# jumper_bed_M.net
KiCad netlist of a schematic drawn in EAGLE
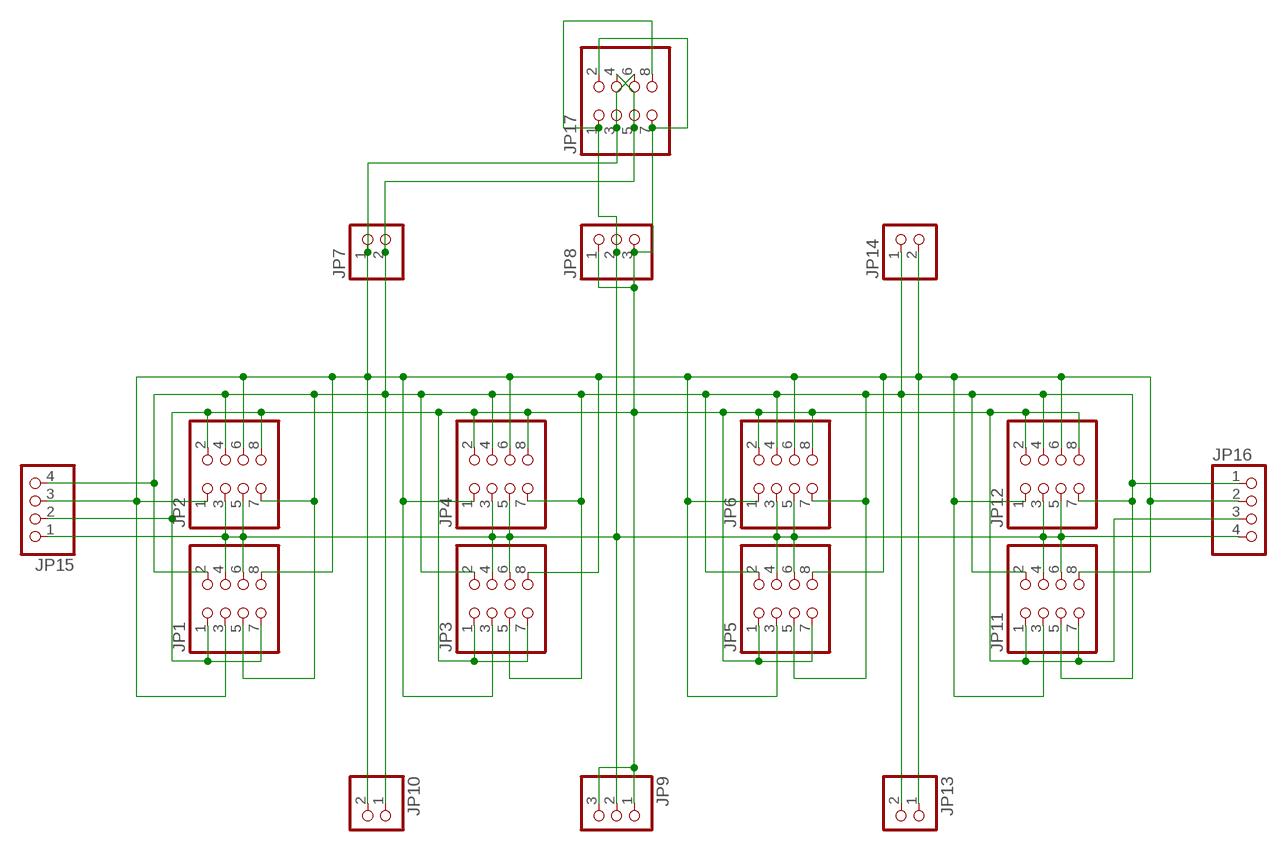
[diagram p0: schematic, sheet 1]

(export (version "E")
  (design (tool "Eeschema 10.0.6"))
  (components
    (comp (ref "JP1")
      (value "PINHD-2X4")
      (footprint "eagle-import:2X04")
      (libsource (lib "eagle-import") (part "PINHD-2X4"))
    )
    (comp (ref "JP2")
      (value "PINHD-2X4")
      (footprint "eagle-import:2X04")
      (libsource (lib "eagle-import") (part "PINHD-2X4"))
    )
    (comp (ref "JP3")
      (value "PINHD-2X4")
      (footprint "eagle-import:2X04")
      (libsource (lib "eagle-import") (part "PINHD-2X4"))
    )
    (comp (ref "JP4")
      (value "PINHD-2X4")
      (footprint "eagle-import:2X04")
      (libsource (lib "eagle-import") (part "PINHD-2X4"))
    )
    (comp (ref "JP5")
      (value "PINHD-2X4")
      (footprint "eagle-import:2X04")
      (libsource (lib "eagle-import") (part "PINHD-2X4"))
    )
    (comp (ref "JP6")
      (value "PINHD-2X4")
      (footprint "eagle-import:2X04")
      (libsource (lib "eagle-import") (part "PINHD-2X4"))
    )
    (comp (ref "JP7")
      (value "PINHD-1X2/90")
      (footprint "eagle-import:1X02_90")
      (libsource (lib "eagle-import") (part "PINHD-1X2/90"))
    )
    (comp (ref "JP8")
      (value "PINHD-1X3/90")
      (footprint "eagle-import:1X03_90")
      (libsource (lib "eagle-import") (part "PINHD-1X3/90"))
    )
    (comp (ref "JP9")
      (value "PINHD-1X31X03/90F")
      (footprint "eagle-import:1X03_90F")
      (libsource (lib "eagle-import") (part "PINHD-1X31X03/90F"))
    )
    (comp (ref "JP10")
      (value "PINHD-1X21X02/90F")
      (footprint "eagle-import:1X02_90F")
      (libsource (lib "eagle-import") (part "PINHD-1X21X02/90F"))
    )
    (comp (ref "JP11")
      (value "PINHD-2X4")
      (footprint "eagle-import:2X04")
      (libsource (lib "eagle-import") (part "PINHD-2X4"))
    )
    (comp (ref "JP12")
      (value "PINHD-2X4")
      (footprint "eagle-import:2X04")
      (libsource (lib "eagle-import") (part "PINHD-2X4"))
    )
    (comp (ref "JP13")
      (value "PINHD-1X21X02/90F")
      (footprint "eagle-import:1X02_90F")
      (libsource (lib "eagle-import") (part "PINHD-1X21X02/90F"))
    )
    (comp (ref "JP14")
      (value "PINHD-1X2/90")
      (footprint "eagle-import:1X02_90")
      (libsource (lib "eagle-import") (part "PINHD-1X2/90"))
    )
    (comp (ref "JP15")
      (value "PINHD-1X4")
      (footprint "eagle-import:1X04")
      (libsource (lib "eagle-import") (part "PINHD-1X4"))
    )
    (comp (ref "JP16")
      (value "PINHD-1X4")
      (footprint "eagle-import:1X04")
      (libsource (lib "eagle-import") (part "PINHD-1X4"))
    )
    (comp (ref "JP17")
      (value "PINHD-2X4/90")
      (footprint "eagle-import:2X04_90")
      (libsource (lib "eagle-import") (part "PINHD-2X4/90"))
    )
  )
  (nets
    (net (code "1") (name "Net-(JP1-Pad1)") (class "Default")
      (node (ref "JP1") (pin "1") (pinfunction "1_1") (pintype "passive"))
      (node (ref "JP1") (pin "7") (pinfunction "7_7") (pintype "passive"))
      (node (ref "JP11") (pin "1") (pinfunction "1_1") (pintype "passive"))
      (node (ref "JP11") (pin "7") (pinfunction "7_7") (pintype "passive"))
      (node (ref "JP12") (pin "2") (pinfunction "2_2") (pintype "passive"))
      (node (ref "JP12") (pin "8") (pinfunction "8_8") (pintype "passive"))
      (node (ref "JP15") (pin "2") (pinfunction "2_2") (pintype "passive"))
      (node (ref "JP16") (pin "3") (pinfunction "3_3") (pintype "passive"))
      (node (ref "JP17") (pin "2") (pinfunction "2_2") (pintype "passive"))
      (node (ref "JP17") (pin "7") (pinfunction "7_7") (pintype "passive"))
      (node (ref "JP2") (pin "2") (pinfunction "2_2") (pintype "passive"))
      (node (ref "JP2") (pin "8") (pinfunction "8_8") (pintype "passive"))
      (node (ref "JP3") (pin "1") (pinfunction "1_1") (pintype "passive"))
      (node (ref "JP3") (pin "7") (pinfunction "7_7") (pintype "passive"))
      (node (ref "JP4") (pin "2") (pinfunction "2_2") (pintype "passive"))
      (node (ref "JP4") (pin "8") (pinfunction "8_8") (pintype "passive"))
      (node (ref "JP5") (pin "1") (pinfunction "1_1") (pintype "passive"))
      (node (ref "JP5") (pin "7") (pinfunction "7_7") (pintype "passive"))
      (node (ref "JP6") (pin "2") (pinfunction "2_2") (pintype "passive"))
      (node (ref "JP6") (pin "8") (pinfunction "8_8") (pintype "passive"))
      (node (ref "JP8") (pin "1") (pinfunction "1_1") (pintype "passive"))
      (node (ref "JP8") (pin "3") (pinfunction "3_3") (pintype "passive"))
      (node (ref "JP9") (pin "1") (pinfunction "1_1") (pintype "passive"))
      (node (ref "JP9") (pin "3") (pinfunction "3_3") (pintype "passive"))
    )
    (net (code "2") (name "Net-(JP1-Pad2)") (class "Default")
      (node (ref "JP1") (pin "2") (pinfunction "2_2") (pintype "passive"))
      (node (ref "JP1") (pin "5") (pinfunction "5_5") (pintype "passive"))
      (node (ref "JP10") (pin "1") (pinfunction "1_1") (pintype "passive"))
      (node (ref "JP11") (pin "2") (pinfunction "2_2") (pintype "passive"))
      (node (ref "JP11") (pin "5") (pinfunction "5_5") (pintype "passive"))
      (node (ref "JP12") (pin "4") (pinfunction "4_4") (pintype "passive"))
      (node (ref "JP12") (pin "7") (pinfunction "7_7") (pintype "passive"))
      (node (ref "JP13") (pin "2") (pinfunction "2_2") (pintype "passive"))
      (node (ref "JP14") (pin "1") (pinfunction "1_1") (pintype "passive"))
      (node (ref "JP15") (pin "4") (pinfunction "4_4") (pintype "passive"))
      (node (ref "JP16") (pin "1") (pinfunction "1_1") (pintype "passive"))
      (node (ref "JP17") (pin "4") (pinfunction "4_4") (pintype "passive"))
      (node (ref "JP17") (pin "5") (pinfunction "5_5") (pintype "passive"))
      (node (ref "JP2") (pin "4") (pinfunction "4_4") (pintype "passive"))
      (node (ref "JP2") (pin "7") (pinfunction "7_7") (pintype "passive"))
      (node (ref "JP3") (pin "2") (pinfunction "2_2") (pintype "passive"))
      (node (ref "JP3") (pin "5") (pinfunction "5_5") (pintype "passive"))
      (node (ref "JP4") (pin "4") (pinfunction "4_4") (pintype "passive"))
      (node (ref "JP4") (pin "7") (pinfunction "7_7") (pintype "passive"))
      (node (ref "JP5") (pin "2") (pinfunction "2_2") (pintype "passive"))
      (node (ref "JP5") (pin "5") (pinfunction "5_5") (pintype "passive"))
      (node (ref "JP6") (pin "4") (pinfunction "4_4") (pintype "passive"))
      (node (ref "JP6") (pin "7") (pinfunction "7_7") (pintype "passive"))
      (node (ref "JP7") (pin "2") (pinfunction "2_2") (pintype "passive"))
    )
    (net (code "3") (name "Net-(JP1-Pad3)") (class "Default")
      (node (ref "JP1") (pin "3") (pinfunction "3_3") (pintype "passive"))
      (node (ref "JP1") (pin "8") (pinfunction "8_8") (pintype "passive"))
      (node (ref "JP10") (pin "2") (pinfunction "2_2") (pintype "passive"))
      (node (ref "JP11") (pin "3") (pinfunction "3_3") (pintype "passive"))
      (node (ref "JP11") (pin "8") (pinfunction "8_8") (pintype "passive"))
      (node (ref "JP12") (pin "1") (pinfunction "1_1") (pintype "passive"))
      (node (ref "JP12") (pin "6") (pinfunction "6_6") (pintype "passive"))
      (node (ref "JP13") (pin "1") (pinfunction "1_1") (pintype "passive"))
      (node (ref "JP14") (pin "2") (pinfunction "2_2") (pintype "passive"))
      (node (ref "JP15") (pin "3") (pinfunction "3_3") (pintype "passive"))
      (node (ref "JP16") (pin "2") (pinfunction "2_2") (pintype "passive"))
      (node (ref "JP17") (pin "3") (pinfunction "3_3") (pintype "passive"))
      (node (ref "JP17") (pin "6") (pinfunction "6_6") (pintype "passive"))
      (node (ref "JP2") (pin "1") (pinfunction "1_1") (pintype "passive"))
      (node (ref "JP2") (pin "6") (pinfunction "6_6") (pintype "passive"))
      (node (ref "JP3") (pin "3") (pinfunction "3_3") (pintype "passive"))
      (node (ref "JP3") (pin "8") (pinfunction "8_8") (pintype "passive"))
      (node (ref "JP4") (pin "1") (pinfunction "1_1") (pintype "passive"))
      (node (ref "JP4") (pin "6") (pinfunction "6_6") (pintype "passive"))
      (node (ref "JP5") (pin "3") (pinfunction "3_3") (pintype "passive"))
      (node (ref "JP5") (pin "8") (pinfunction "8_8") (pintype "passive"))
      (node (ref "JP6") (pin "1") (pinfunction "1_1") (pintype "passive"))
      (node (ref "JP6") (pin "6") (pinfunction "6_6") (pintype "passive"))
      (node (ref "JP7") (pin "1") (pinfunction "1_1") (pintype "passive"))
    )
    (net (code "4") (name "Net-(JP1-Pad4)") (class "Default")
      (node (ref "JP1") (pin "4") (pinfunction "4_4") (pintype "passive"))
      (node (ref "JP1") (pin "6") (pinfunction "6_6") (pintype "passive"))
      (node (ref "JP11") (pin "4") (pinfunction "4_4") (pintype "passive"))
      (node (ref "JP11") (pin "6") (pinfunction "6_6") (pintype "passive"))
      (node (ref "JP12") (pin "3") (pinfunction "3_3") (pintype "passive"))
      (node (ref "JP12") (pin "5") (pinfunction "5_5") (pintype "passive"))
      (node (ref "JP15") (pin "1") (pinfunction "1_1") (pintype "passive"))
      (node (ref "JP16") (pin "4") (pinfunction "4_4") (pintype "passive"))
      (node (ref "JP17") (pin "1") (pinfunction "1_1") (pintype "passive"))
      (node (ref "JP17") (pin "8") (pinfunction "8_8") (pintype "passive"))
      (node (ref "JP2") (pin "3") (pinfunction "3_3") (pintype "passive"))
      (node (ref "JP2") (pin "5") (pinfunction "5_5") (pintype "passive"))
      (node (ref "JP3") (pin "4") (pinfunction "4_4") (pintype "passive"))
      (node (ref "JP3") (pin "6") (pinfunction "6_6") (pintype "passive"))
      (node (ref "JP4") (pin "3") (pinfunction "3_3") (pintype "passive"))
      (node (ref "JP4") (pin "5") (pinfunction "5_5") (pintype "passive"))
      (node (ref "JP5") (pin "4") (pinfunction "4_4") (pintype "passive"))
      (node (ref "JP5") (pin "6") (pinfunction "6_6") (pintype "passive"))
      (node (ref "JP6") (pin "3") (pinfunction "3_3") (pintype "passive"))
      (node (ref "JP6") (pin "5") (pinfunction "5_5") (pintype "passive"))
      (node (ref "JP8") (pin "2") (pinfunction "2_2") (pintype "passive"))
      (node (ref "JP9") (pin "2") (pinfunction "2_2") (pintype "passive"))
    )
  )
)
